# Sch_TPA3116.net
KiCad netlist of a schematic drawn in Altium Designer
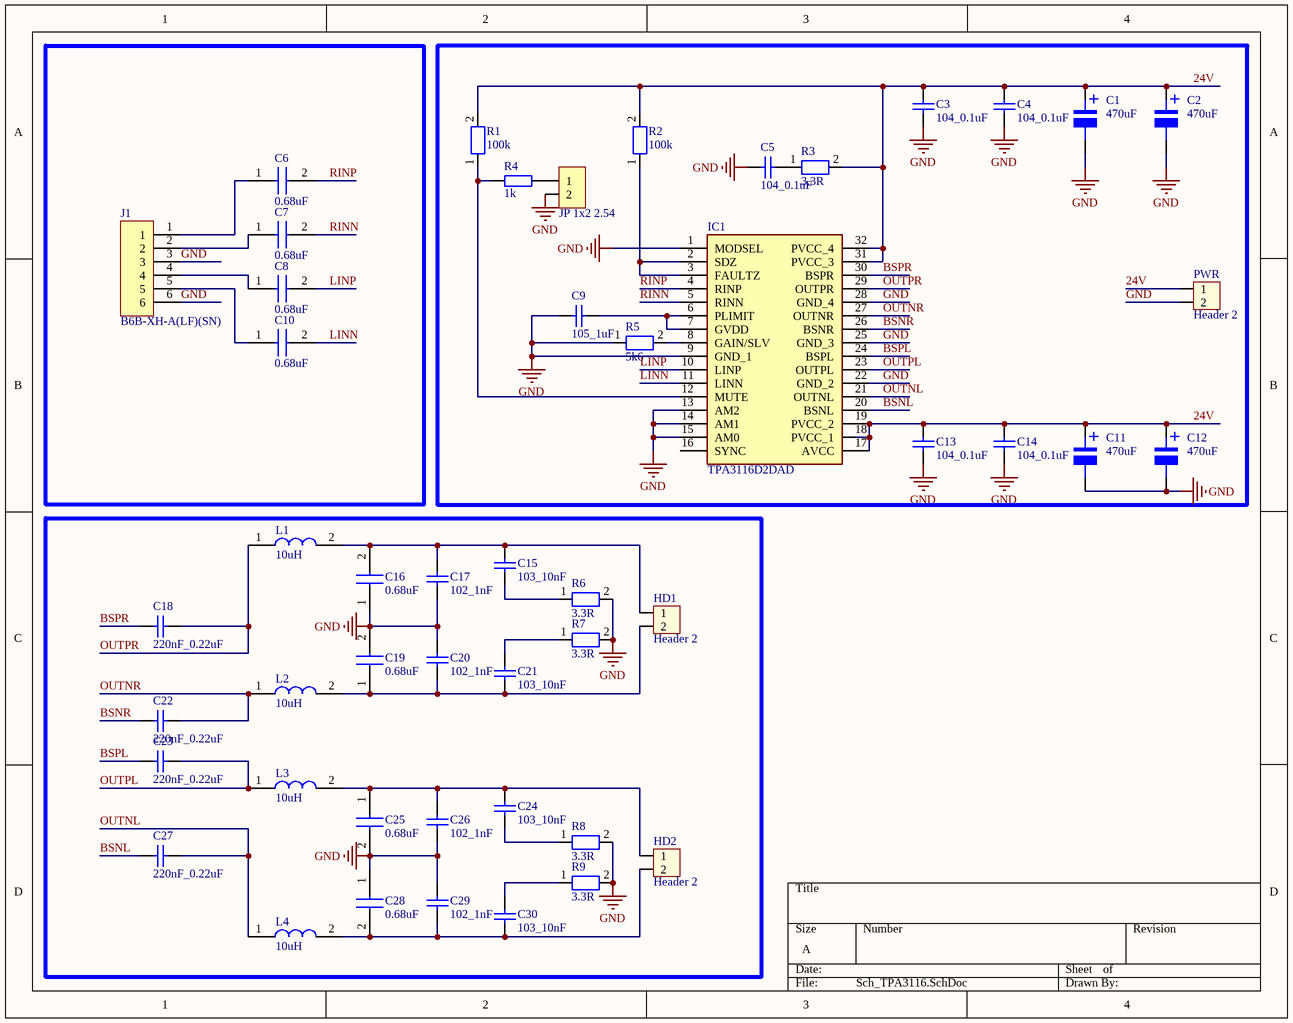
[diagram p0: Sch_TPA3116.SchDoc]

(export (version "E")
  (design (tool "Eeschema 10.0.6"))
  (components
    (comp (ref "C1")
      (value "470uF")
      (footprint "tu nhom 10 (G)")
      (description "Dán")
      (libsource (lib "Tu dien") (part "Tu Nhom 470uF 35V"))
    )
    (comp (ref "C2")
      (value "470uF")
      (footprint "tu nhom 10 (G)")
      (description "Dán")
      (libsource (lib "Tu dien") (part "Tu Nhom 470uF 35V"))
    )
    (comp (ref "C3")
      (value "104_0.1uF")
      (footprint "tu 0805")
      (description "Dán")
      (libsource (lib "Tu dien") (part "Tu 0805 104 50V 10%"))
    )
    (comp (ref "C4")
      (value "104_0.1uF")
      (footprint "tu 0805")
      (description "Dán")
      (libsource (lib "Tu dien") (part "Tu 0805 104 50V 10%"))
    )
    (comp (ref "C5")
      (value "104_0.1uF")
      (footprint "tu 0805")
      (description "Dán")
      (libsource (lib "Tu dien") (part "Tu 0805 104 50V 10%"))
    )
    (comp (ref "C6")
      (value "0.68uF")
      (footprint "SamacSys:B32529C0684J000")
      (description "Capacitor")
      (fields (field (name "MANUFACTURER_PART_NUMBER") "B32529C0684J000"))
      (libsource (lib "test") (part "0.68uF/63V"))
    )
    (comp (ref "C7")
      (value "0.68uF")
      (footprint "SamacSys:B32529C0684J000")
      (description "Capacitor")
      (fields (field (name "MANUFACTURER_PART_NUMBER") "B32529C0684J000"))
      (libsource (lib "test") (part "0.68uF/63V"))
    )
    (comp (ref "C8")
      (value "0.68uF")
      (footprint "SamacSys:B32529C0684J000")
      (description "Capacitor")
      (fields (field (name "MANUFACTURER_PART_NUMBER") "B32529C0684J000"))
      (libsource (lib "test") (part "0.68uF/63V"))
    )
    (comp (ref "C9")
      (value "105_1uF")
      (footprint "tu 0805")
      (description "Dán")
      (libsource (lib "Tu dien") (part "Tu 0805 105 50V 10%"))
    )
    (comp (ref "C10")
      (value "0.68uF")
      (footprint "SamacSys:B32529C0684J000")
      (description "Capacitor")
      (fields (field (name "MANUFACTURER_PART_NUMBER") "B32529C0684J000"))
      (libsource (lib "test") (part "0.68uF/63V"))
    )
    (comp (ref "C11")
      (value "470uF")
      (footprint "tu nhom 10 (G)")
      (description "Dán")
      (libsource (lib "Tu dien") (part "Tu Nhom 470uF 35V"))
    )
    (comp (ref "C12")
      (value "470uF")
      (footprint "tu nhom 10 (G)")
      (description "Dán")
      (libsource (lib "Tu dien") (part "Tu Nhom 470uF 35V"))
    )
    (comp (ref "C13")
      (value "104_0.1uF")
      (footprint "tu 0805")
      (description "Dán")
      (libsource (lib "Tu dien") (part "Tu 0805 104 50V 10%"))
    )
    (comp (ref "C14")
      (value "104_0.1uF")
      (footprint "tu 0805")
      (description "Dán")
      (libsource (lib "Tu dien") (part "Tu 0805 104 50V 10%"))
    )
    (comp (ref "C15")
      (value "103_10nF")
      (footprint "tu 0603")
      (description "Dán")
      (libsource (lib "Tu dien") (part "Tu 0603 103 50V 10%"))
    )
    (comp (ref "C16")
      (value "0.68uF")
      (footprint "SamacSys:B32529C0684J000")
      (description "Capacitor")
      (fields (field (name "MANUFACTURER_PART_NUMBER") "B32529C0684J000"))
      (libsource (lib "test") (part "0.68uF/63V"))
    )
    (comp (ref "C17")
      (value "102_1nF")
      (footprint "tu 0805")
      (description "Dán")
      (libsource (lib "Tu dien") (part "Tu 0805 102 50V 10%"))
    )
    (comp (ref "C18")
      (value "220nF_0.22uF")
      (footprint "tu 0805")
      (description "Dán")
      (libsource (lib "Tu dien") (part "Tu 0805 220nF 50V 10%"))
    )
    (comp (ref "C19")
      (value "0.68uF")
      (footprint "SamacSys:B32529C0684J000")
      (description "Capacitor")
      (fields (field (name "MANUFACTURER_PART_NUMBER") "B32529C0684J000"))
      (libsource (lib "test") (part "0.68uF/63V"))
    )
    (comp (ref "C20")
      (value "102_1nF")
      (footprint "tu 0805")
      (description "Dán")
      (libsource (lib "Tu dien") (part "Tu 0805 102 50V 10%"))
    )
    (comp (ref "C21")
      (value "103_10nF")
      (footprint "tu 0603")
      (description "Dán")
      (libsource (lib "Tu dien") (part "Tu 0603 103 50V 10%"))
    )
    (comp (ref "C22")
      (value "220nF_0.22uF")
      (footprint "tu 0805")
      (description "Dán")
      (libsource (lib "Tu dien") (part "Tu 0805 220nF 50V 10%"))
    )
    (comp (ref "C23")
      (value "220nF_0.22uF")
      (footprint "tu 0805")
      (description "Dán")
      (libsource (lib "Tu dien") (part "Tu 0805 220nF 50V 10%"))
    )
    (comp (ref "C24")
      (value "103_10nF")
      (footprint "tu 0603")
      (description "Dán")
      (libsource (lib "Tu dien") (part "Tu 0603 103 50V 10%"))
    )
    (comp (ref "C25")
      (value "0.68uF")
      (footprint "SamacSys:B32529C0684J000")
      (description "Capacitor")
      (fields (field (name "MANUFACTURER_PART_NUMBER") "B32529C0684J000"))
      (libsource (lib "test") (part "0.68uF/63V"))
    )
    (comp (ref "C26")
      (value "102_1nF")
      (footprint "tu 0805")
      (description "Dán")
      (libsource (lib "Tu dien") (part "Tu 0805 102 50V 10%"))
    )
    (comp (ref "C27")
      (value "220nF_0.22uF")
      (footprint "tu 0805")
      (description "Dán")
      (libsource (lib "Tu dien") (part "Tu 0805 220nF 50V 10%"))
    )
    (comp (ref "C28")
      (value "0.68uF")
      (footprint "SamacSys:B32529C0684J000")
      (description "Capacitor")
      (fields (field (name "MANUFACTURER_PART_NUMBER") "B32529C0684J000"))
      (libsource (lib "test") (part "0.68uF/63V"))
    )
    (comp (ref "C29")
      (value "102_1nF")
      (footprint "tu 0805")
      (description "Dán")
      (libsource (lib "Tu dien") (part "Tu 0805 102 50V 10%"))
    )
    (comp (ref "C30")
      (value "103_10nF")
      (footprint "tu 0603")
      (description "Dán")
      (libsource (lib "Tu dien") (part "Tu 0603 103 50V 10%"))
    )
    (comp (ref "HD1")
      (value "Header 2")
      (footprint "HED2")
      (description "Header 2 (Green)")
      (libsource (lib "syhaunguyen") (part "Hed2"))
    )
    (comp (ref "HD2")
      (value "Header 2")
      (footprint "HED2")
      (description "Header 2 (Green)")
      (libsource (lib "syhaunguyen") (part "Hed2"))
    )
    (comp (ref "IC1")
      (value "TPA3116D2DAD")
      (footprint "SamacSys:SOP65P810X120-32N")
      (description "Integrated Circuit")
      (fields (field (name "MOUSER PART NUMBER") "595-TPA3116D2DAD"))
      (libsource (lib "test") (part "TPA3116D2DAD"))
    )
    (comp (ref "J1")
      (value "B6B-XH-A(LF)(SN)")
      (footprint "CON6_100_B6B-XH-A_TH_ST")
      (description "6 Pins, 1 Row 2.54mm Pitch, straight Connector, male")
      (fields (field (name "MANUFACTURER") "JST") (field (name "MATING PART NUMBER") "XHP-6"))
      (libsource (lib "Connector") (part "CON-PLG_6X1-100-ST-TH"))
    )
    (comp (ref "JP1")
      (value "JP 1x2 2.54")
      (footprint "JP 1x2 DT")
      (description "Cắm")
      (libsource (lib "Jump") (part "JP 1x2 2.54 Duc Thang"))
    )
    (comp (ref "L1")
      (value "10uH")
      (footprint "ind_dr125_10uH")
      (libsource (lib "test") (part "ind_dr125_100_10uH"))
    )
    (comp (ref "L2")
      (value "10uH")
      (footprint "ind_dr125_10uH")
      (libsource (lib "test") (part "ind_dr125_100_10uH"))
    )
    (comp (ref "L3")
      (value "10uH")
      (footprint "ind_dr125_10uH")
      (libsource (lib "test") (part "ind_dr125_100_10uH"))
    )
    (comp (ref "L4")
      (value "10uH")
      (footprint "ind_dr125_10uH")
      (libsource (lib "test") (part "ind_dr125_100_10uH"))
    )
    (comp (ref "PWR")
      (value "Header 2")
      (footprint "HED2")
      (description "Header 2 (Green)")
      (libsource (lib "syhaunguyen") (part "Hed2"))
    )
    (comp (ref "R1")
      (value "100k")
      (footprint "Tro SMD 0805")
      (description "Resistor")
      (fields
        (field (name "MANUFACTURER_PART_NUMBER") "CR0603-FX-1202ELF")
        (field (name "MOUSER PART NUMBER") "652-CR0603FX-1202ELF")
      )
      (libsource (lib "test") (part "R0805_100k_1%"))
    )
    (comp (ref "R2")
      (value "100k")
      (footprint "Tro SMD 0805")
      (description "Resistor")
      (fields
        (field (name "MANUFACTURER_PART_NUMBER") "CR0603-FX-1202ELF")
        (field (name "MOUSER PART NUMBER") "652-CR0603FX-1202ELF")
      )
      (libsource (lib "test") (part "R0805_100k_1%"))
    )
    (comp (ref "R3")
      (value "3.3R")
      (footprint "Tro SMD 1206")
      (description "Resistor")
      (fields
        (field (name "MANUFACTURER_PART_NUMBER") "CR0603-FX-1202ELF")
        (field (name "MOUSER PART NUMBER") "652-CR0603FX-1202ELF")
      )
      (libsource (lib "test") (part "R1206_3.3R_1/2W"))
    )
    (comp (ref "R4")
      (value "1k")
      (footprint "tro smd 0805")
      (description "Dán")
      (libsource (lib "Dien Tro") (part "Tro 0805 1% 1k"))
    )
    (comp (ref "R5")
      (value "5k6")
      (footprint "Tro SMD 0805")
      (description "Resistor")
      (fields
        (field (name "MANUFACTURER_PART_NUMBER") "CR0603-FX-1202ELF")
        (field (name "MOUSER PART NUMBER") "652-CR0603FX-1202ELF")
      )
      (libsource (lib "test") (part "R0805_5k6_1%"))
    )
    (comp (ref "R6")
      (value "3.3R")
      (footprint "Tro SMD 1206")
      (description "Resistor")
      (fields
        (field (name "MANUFACTURER_PART_NUMBER") "CR0603-FX-1202ELF")
        (field (name "MOUSER PART NUMBER") "652-CR0603FX-1202ELF")
      )
      (libsource (lib "test") (part "R1206_3.3R_1/2W"))
    )
    (comp (ref "R7")
      (value "3.3R")
      (footprint "Tro SMD 1206")
      (description "Resistor")
      (fields
        (field (name "MANUFACTURER_PART_NUMBER") "CR0603-FX-1202ELF")
        (field (name "MOUSER PART NUMBER") "652-CR0603FX-1202ELF")
      )
      (libsource (lib "test") (part "R1206_3.3R_1/2W"))
    )
    (comp (ref "R8")
      (value "3.3R")
      (footprint "Tro SMD 1206")
      (description "Resistor")
      (fields
        (field (name "MANUFACTURER_PART_NUMBER") "CR0603-FX-1202ELF")
        (field (name "MOUSER PART NUMBER") "652-CR0603FX-1202ELF")
      )
      (libsource (lib "test") (part "R1206_3.3R_1/2W"))
    )
    (comp (ref "R9")
      (value "3.3R")
      (footprint "Tro SMD 1206")
      (description "Resistor")
      (fields
        (field (name "MANUFACTURER_PART_NUMBER") "CR0603-FX-1202ELF")
        (field (name "MOUSER PART NUMBER") "652-CR0603FX-1202ELF")
      )
      (libsource (lib "test") (part "R1206_3.3R_1/2W"))
    )
  )
  (nets
    (net (code "1") (name "/24V") (class "Default")
      (node (ref "C1") (pin "1") (pinfunction "1_1") (pintype "passive"))
      (node (ref "C11") (pin "1") (pinfunction "1_1") (pintype "passive"))
      (node (ref "C12") (pin "1") (pinfunction "1_1") (pintype "passive"))
      (node (ref "C13") (pin "1") (pinfunction "1_1") (pintype "passive"))
      (node (ref "C14") (pin "1") (pinfunction "1_1") (pintype "passive"))
      (node (ref "C2") (pin "1") (pinfunction "1_1") (pintype "passive"))
      (node (ref "C3") (pin "1") (pinfunction "1_1") (pintype "passive"))
      (node (ref "C4") (pin "1") (pinfunction "1_1") (pintype "passive"))
      (node (ref "IC1") (pin "17") (pinfunction "AVCC_17") (pintype "passive"))
      (node (ref "IC1") (pin "18") (pinfunction "PVCC_1_18") (pintype "passive"))
      (node (ref "IC1") (pin "19") (pinfunction "PVCC_2_19") (pintype "passive"))
      (node (ref "IC1") (pin "31") (pinfunction "PVCC_3_31") (pintype "passive"))
      (node (ref "IC1") (pin "32") (pinfunction "PVCC_4_32") (pintype "passive"))
      (node (ref "PWR") (pin "1") (pinfunction "1_1") (pintype "passive"))
      (node (ref "R1") (pin "2") (pinfunction "2_2") (pintype "passive"))
      (node (ref "R2") (pin "2") (pinfunction "2_2") (pintype "passive"))
      (node (ref "R3") (pin "2") (pinfunction "2_2") (pintype "passive"))
    )
    (net (code "2") (name "/BSNL") (class "Default")
      (node (ref "C27") (pin "2") (pinfunction "2_2") (pintype "passive"))
      (node (ref "IC1") (pin "20") (pinfunction "BSNL_20") (pintype "passive"))
    )
    (net (code "3") (name "/BSNR") (class "Default")
      (node (ref "C22") (pin "2") (pinfunction "2_2") (pintype "passive"))
      (node (ref "IC1") (pin "26") (pinfunction "BSNR_26") (pintype "passive"))
    )
    (net (code "4") (name "/BSPL") (class "Default")
      (node (ref "C23") (pin "2") (pinfunction "2_2") (pintype "passive"))
      (node (ref "IC1") (pin "24") (pinfunction "BSPL_24") (pintype "passive"))
    )
    (net (code "5") (name "/BSPR") (class "Default")
      (node (ref "C18") (pin "2") (pinfunction "2_2") (pintype "passive"))
      (node (ref "IC1") (pin "30") (pinfunction "BSPR_30") (pintype "passive"))
    )
    (net (code "6") (name "/LINN") (class "Default")
      (node (ref "C10") (pin "2") (pinfunction "2_2") (pintype "passive"))
      (node (ref "IC1") (pin "11") (pinfunction "LINN_11") (pintype "passive"))
    )
    (net (code "7") (name "/LINP") (class "Default")
      (node (ref "C8") (pin "2") (pinfunction "2_2") (pintype "passive"))
      (node (ref "IC1") (pin "10") (pinfunction "LINP_10") (pintype "passive"))
    )
    (net (code "8") (name "/OUTNL") (class "Default")
      (node (ref "C27") (pin "1") (pinfunction "1_1") (pintype "passive"))
      (node (ref "IC1") (pin "21") (pinfunction "OUTNL_21") (pintype "passive"))
      (node (ref "L4") (pin "1") (pintype "passive"))
    )
    (net (code "9") (name "/OUTNR") (class "Default")
      (node (ref "C22") (pin "1") (pinfunction "1_1") (pintype "passive"))
      (node (ref "IC1") (pin "27") (pinfunction "OUTNR_27") (pintype "passive"))
      (node (ref "L2") (pin "1") (pintype "passive"))
    )
    (net (code "10") (name "/OUTPL") (class "Default")
      (node (ref "C23") (pin "1") (pinfunction "1_1") (pintype "passive"))
      (node (ref "IC1") (pin "23") (pinfunction "OUTPL_23") (pintype "passive"))
      (node (ref "L3") (pin "1") (pintype "passive"))
    )
    (net (code "11") (name "/OUTPR") (class "Default")
      (node (ref "C18") (pin "1") (pinfunction "1_1") (pintype "passive"))
      (node (ref "IC1") (pin "29") (pinfunction "OUTPR_29") (pintype "passive"))
      (node (ref "L1") (pin "1") (pintype "passive"))
    )
    (net (code "12") (name "/RINN") (class "Default")
      (node (ref "C7") (pin "2") (pinfunction "2_2") (pintype "passive"))
      (node (ref "IC1") (pin "5") (pinfunction "RINN_5") (pintype "passive"))
    )
    (net (code "13") (name "/RINP") (class "Default")
      (node (ref "C6") (pin "2") (pinfunction "2_2") (pintype "passive"))
      (node (ref "IC1") (pin "4") (pinfunction "RINP_4") (pintype "passive"))
    )
    (net (code "14") (name "GND") (class "Default")
      (node (ref "C1") (pin "2") (pinfunction "2_2") (pintype "passive"))
      (node (ref "C11") (pin "2") (pinfunction "2_2") (pintype "passive"))
      (node (ref "C12") (pin "2") (pinfunction "2_2") (pintype "passive"))
      (node (ref "C13") (pin "2") (pinfunction "2_2") (pintype "passive"))
      (node (ref "C14") (pin "2") (pinfunction "2_2") (pintype "passive"))
      (node (ref "C16") (pin "1") (pinfunction "1_1") (pintype "passive"))
      (node (ref "C17") (pin "2") (pinfunction "2_2") (pintype "passive"))
      (node (ref "C19") (pin "2") (pinfunction "2_2") (pintype "passive"))
      (node (ref "C2") (pin "2") (pinfunction "2_2") (pintype "passive"))
      (node (ref "C20") (pin "1") (pinfunction "1_1") (pintype "passive"))
      (node (ref "C25") (pin "2") (pinfunction "2_2") (pintype "passive"))
      (node (ref "C26") (pin "1") (pinfunction "1_1") (pintype "passive"))
      (node (ref "C28") (pin "1") (pinfunction "1_1") (pintype "passive"))
      (node (ref "C29") (pin "2") (pinfunction "2_2") (pintype "passive"))
      (node (ref "C3") (pin "2") (pinfunction "2_2") (pintype "passive"))
      (node (ref "C4") (pin "2") (pinfunction "2_2") (pintype "passive"))
      (node (ref "C5") (pin "2") (pinfunction "2_2") (pintype "passive"))
      (node (ref "C9") (pin "2") (pinfunction "2_2") (pintype "passive"))
      (node (ref "IC1") (pin "1") (pinfunction "MODSEL_1") (pintype "passive"))
      (node (ref "IC1") (pin "13") (pinfunction "AM2_13") (pintype "passive"))
      (node (ref "IC1") (pin "14") (pinfunction "AM1_14") (pintype "passive"))
      (node (ref "IC1") (pin "15") (pinfunction "AM0_15") (pintype "passive"))
      (node (ref "IC1") (pin "22") (pinfunction "GND_2_22") (pintype "passive"))
      (node (ref "IC1") (pin "25") (pinfunction "GND_3_25") (pintype "passive"))
      (node (ref "IC1") (pin "28") (pinfunction "GND_4_28") (pintype "passive"))
      (node (ref "IC1") (pin "9") (pinfunction "GND_1_9") (pintype "passive"))
      (node (ref "J1") (pin "3") (pinfunction "3_3") (pintype "passive"))
      (node (ref "J1") (pin "6") (pinfunction "6_6") (pintype "passive"))
      (node (ref "JP1") (pin "2") (pinfunction "2_2") (pintype "passive"))
      (node (ref "PWR") (pin "2") (pinfunction "2_2") (pintype "passive"))
      (node (ref "R5") (pin "1") (pinfunction "1_1") (pintype "passive"))
      (node (ref "R6") (pin "2") (pinfunction "2_2") (pintype "passive"))
      (node (ref "R7") (pin "2") (pinfunction "2_2") (pintype "passive"))
      (node (ref "R8") (pin "2") (pinfunction "2_2") (pintype "passive"))
      (node (ref "R9") (pin "2") (pinfunction "2_2") (pintype "passive"))
    )
    (net (code "15") (name "Net-(C5-Pad1)") (class "Default")
      (node (ref "C5") (pin "1") (pinfunction "1_1") (pintype "passive"))
      (node (ref "R3") (pin "1") (pinfunction "1_1") (pintype "passive"))
    )
    (net (code "16") (name "Net-(C6-Pad1)") (class "Default")
      (node (ref "C6") (pin "1") (pinfunction "1_1") (pintype "passive"))
      (node (ref "J1") (pin "1") (pinfunction "1_1") (pintype "passive"))
    )
    (net (code "17") (name "Net-(C7-Pad1)") (class "Default")
      (node (ref "C7") (pin "1") (pinfunction "1_1") (pintype "passive"))
      (node (ref "J1") (pin "2") (pinfunction "2_2") (pintype "passive"))
    )
    (net (code "18") (name "Net-(C8-Pad1)") (class "Default")
      (node (ref "C8") (pin "1") (pinfunction "1_1") (pintype "passive"))
      (node (ref "J1") (pin "4") (pinfunction "4_4") (pintype "passive"))
    )
    (net (code "19") (name "Net-(C10-Pad1)") (class "Default")
      (node (ref "C10") (pin "1") (pinfunction "1_1") (pintype "passive"))
      (node (ref "J1") (pin "5") (pinfunction "5_5") (pintype "passive"))
    )
    (net (code "20") (name "Net-(C15-Pad1)") (class "Default")
      (node (ref "C15") (pin "1") (pinfunction "1_1") (pintype "passive"))
      (node (ref "C16") (pin "2") (pinfunction "2_2") (pintype "passive"))
      (node (ref "C17") (pin "1") (pinfunction "1_1") (pintype "passive"))
      (node (ref "HD1") (pin "1") (pinfunction "1_1") (pintype "passive"))
      (node (ref "L1") (pin "2") (pintype "passive"))
    )
    (net (code "21") (name "Net-(C15-Pad2)") (class "Default")
      (node (ref "C15") (pin "2") (pinfunction "2_2") (pintype "passive"))
      (node (ref "R6") (pin "1") (pinfunction "1_1") (pintype "passive"))
    )
    (net (code "22") (name "Net-(C19-Pad1)") (class "Default")
      (node (ref "C19") (pin "1") (pinfunction "1_1") (pintype "passive"))
      (node (ref "C20") (pin "2") (pinfunction "2_2") (pintype "passive"))
      (node (ref "C21") (pin "2") (pinfunction "2_2") (pintype "passive"))
      (node (ref "HD1") (pin "2") (pinfunction "2_2") (pintype "passive"))
      (node (ref "L2") (pin "2") (pintype "passive"))
    )
    (net (code "23") (name "Net-(C21-Pad1)") (class "Default")
      (node (ref "C21") (pin "1") (pinfunction "1_1") (pintype "passive"))
      (node (ref "R7") (pin "1") (pinfunction "1_1") (pintype "passive"))
    )
    (net (code "24") (name "Net-(C24-Pad1)") (class "Default")
      (node (ref "C24") (pin "1") (pinfunction "1_1") (pintype "passive"))
      (node (ref "R8") (pin "1") (pinfunction "1_1") (pintype "passive"))
    )
    (net (code "25") (name "Net-(C24-Pad2)") (class "Default")
      (node (ref "C24") (pin "2") (pinfunction "2_2") (pintype "passive"))
      (node (ref "C25") (pin "1") (pinfunction "1_1") (pintype "passive"))
      (node (ref "C26") (pin "2") (pinfunction "2_2") (pintype "passive"))
      (node (ref "HD2") (pin "1") (pinfunction "1_1") (pintype "passive"))
      (node (ref "L3") (pin "2") (pintype "passive"))
    )
    (net (code "26") (name "Net-(C28-Pad2)") (class "Default")
      (node (ref "C28") (pin "2") (pinfunction "2_2") (pintype "passive"))
      (node (ref "C29") (pin "1") (pinfunction "1_1") (pintype "passive"))
      (node (ref "C30") (pin "1") (pinfunction "1_1") (pintype "passive"))
      (node (ref "HD2") (pin "2") (pinfunction "2_2") (pintype "passive"))
      (node (ref "L4") (pin "2") (pintype "passive"))
    )
    (net (code "27") (name "Net-(C30-Pad2)") (class "Default")
      (node (ref "C30") (pin "2") (pinfunction "2_2") (pintype "passive"))
      (node (ref "R9") (pin "1") (pinfunction "1_1") (pintype "passive"))
    )
    (net (code "28") (name "Net-(IC1-FAULTZ)") (class "Default")
      (node (ref "IC1") (pin "2") (pinfunction "SDZ_2") (pintype "passive"))
      (node (ref "IC1") (pin "3") (pinfunction "FAULTZ_3") (pintype "passive"))
      (node (ref "R2") (pin "1") (pinfunction "1_1") (pintype "passive"))
    )
    (net (code "29") (name "Net-(IC1-GAIN{slash}SLV)") (class "Default")
      (node (ref "IC1") (pin "8") (pinfunction "GAIN/SLV_8") (pintype "passive"))
      (node (ref "R5") (pin "2") (pinfunction "2_2") (pintype "passive"))
    )
    (net (code "30") (name "Net-(IC1-GVDD)") (class "Default")
      (node (ref "C9") (pin "1") (pinfunction "1_1") (pintype "passive"))
      (node (ref "IC1") (pin "6") (pinfunction "PLIMIT_6") (pintype "passive"))
      (node (ref "IC1") (pin "7") (pinfunction "GVDD_7") (pintype "passive"))
    )
    (net (code "31") (name "Net-(IC1-MUTE)") (class "Default")
      (node (ref "IC1") (pin "12") (pinfunction "MUTE_12") (pintype "passive"))
      (node (ref "R1") (pin "1") (pinfunction "1_1") (pintype "passive"))
      (node (ref "R4") (pin "1") (pinfunction "1_1") (pintype "passive"))
    )
    (net (code "32") (name "Net-(JP1-Pad1)") (class "Default")
      (node (ref "JP1") (pin "1") (pinfunction "1_1") (pintype "passive"))
      (node (ref "R4") (pin "2") (pinfunction "2_2") (pintype "passive"))
    )
    (net (code "33") (name "unconnected-(IC1-SYNC-Pad16)") (class "Default")
      (node (ref "IC1") (pin "16") (pinfunction "SYNC_16") (pintype "passive"))
    )
  )
)
